# PROC099B_Decoupling_Caps_Reference.net
KiCad netlist of a schematic drawn in Altium Designer
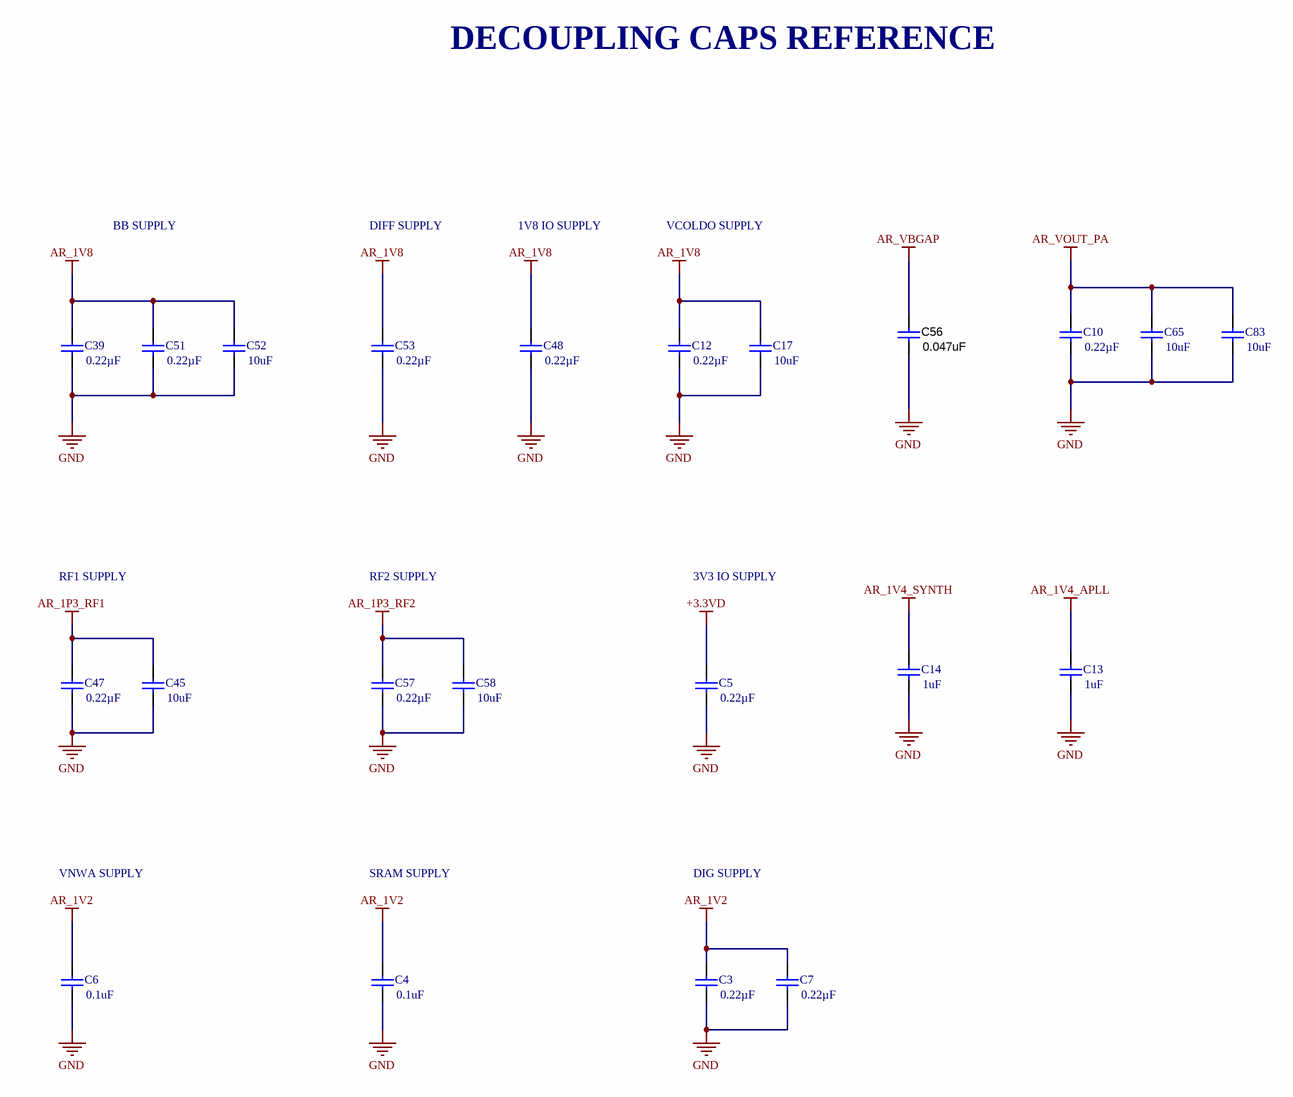
[diagram p0: PROC099B_Decoupling_Caps_Reference.SchDoc]

(export (version "E")
  (design (tool "Eeschema 10.0.6"))
  (components
    (comp (ref "C3")
      (value "GCM155R71C224KE02D")
      (footprint "0402L")
      (description "CAP, CERM, 0.22 µF, 16 V,+/- 10%, X7R, AEC-Q200 Grade 1, 0402")
      (fields (field (name "MANUFACTURER") "MuRata") (field (name "VALUEDISPLAYED") "0.22µF"))
      (libsource (lib "Altium Vault - TI") (part "CMP-0078265-1"))
    )
    (comp (ref "C4")
      (value "GCM155R71C104KA55D")
      (footprint "0402L")
      (description "CAP, CERM, 0.1 uF, 16 V, +/- 10%, X7R, 0402")
      (fields
        (field (name "MANUFACTURER") "MuRata")
        (field (name "VALUEDISPLAYED") "0.1uF")
        (field (name "PUBLISHER") "Texas Instruments")
      )
      (libsource (lib "Altium Vault - TI") (part "CMP-0006351-2"))
    )
    (comp (ref "C5")
      (value "GCM155R71C224KE02D")
      (footprint "0402L")
      (description "CAP, CERM, 0.22 µF, 16 V,+/- 10%, X7R, AEC-Q200 Grade 1, 0402")
      (fields (field (name "MANUFACTURER") "MuRata") (field (name "VALUEDISPLAYED") "0.22µF"))
      (libsource (lib "Altium Vault - TI") (part "CMP-0078265-1"))
    )
    (comp (ref "C6")
      (value "GCM155R71C104KA55D")
      (footprint "0402")
      (description "CAP, CERM, 0.1 uF, 16 V, +/- 10%, X7R, 0402")
      (fields
        (field (name "MANUFACTURER") "MuRata")
        (field (name "VALUEDISPLAYED") "0.1uF")
        (field (name "PUBLISHER") "Texas Instruments")
      )
      (libsource (lib "Altium Vault - TI") (part "Capacitor"))
    )
    (comp (ref "C7")
      (value "GCM155R71C224KE02D")
      (footprint "0402L")
      (description "CAP, CERM, 0.22 µF, 16 V,+/- 10%, X7R, AEC-Q200 Grade 1, 0402")
      (fields (field (name "MANUFACTURER") "MuRata") (field (name "VALUEDISPLAYED") "0.22µF"))
      (libsource (lib "Altium Vault - TI") (part "CMP-0078265-1"))
    )
    (comp (ref "C10")
      (value "GCM155R71C224KE02D")
      (footprint "0402")
      (description "CAP, CERM, 0.22 µF, 16 V,+/- 10%, X7R, AEC-Q200 Grade 1, 0402")
      (fields (field (name "MANUFACTURER") "MuRata") (field (name "VALUEDISPLAYED") "0.22µF"))
      (libsource (lib "Altium Vault - TI") (part "Capacitor"))
    )
    (comp (ref "C12")
      (value "GCM155R71C224KE02D")
      (footprint "0402")
      (description "CAP, CERM, 0.22 µF, 16 V,+/- 10%, X7R, AEC-Q200 Grade 1, 0402")
      (fields (field (name "MANUFACTURER") "MuRata") (field (name "VALUEDISPLAYED") "0.22µF"))
      (libsource (lib "Altium Vault - TI") (part "Capacitor"))
    )
    (comp (ref "C13")
      (value "GCM188R71C105KA64D")
      (footprint "0603")
      (description "CAP, CERM, 1 uF, 16 V, +/- 10%, X7R, AEC-Q200 Grade 1, 0603")
      (fields
        (field (name "MANUFACTURER") "MuRata")
        (field (name "VALUEDISPLAYED") "1uF")
        (field (name "PUBLISHER") "Texas Instruments")
      )
      (libsource (lib "Altium Vault - TI") (part "Capacitor"))
    )
    (comp (ref "C14")
      (value "GCM188R71C105KA64D")
      (footprint "0603")
      (description "CAP, CERM, 1 uF, 16 V, +/- 10%, X7R, AEC-Q200 Grade 1, 0603")
      (fields
        (field (name "MANUFACTURER") "MuRata")
        (field (name "VALUEDISPLAYED") "1uF")
        (field (name "PUBLISHER") "Texas Instruments")
      )
      (libsource (lib "Altium Vault - TI") (part "Capacitor"))
    )
    (comp (ref "C17")
      (value "GCM21BR71A106KE22L")
      (footprint "0805_HV")
      (description "CAP, CERM, 10 uF, 10 V, +/- 10%, X7R, 0805")
      (fields
        (field (name "MANUFACTURER") "MuRata")
        (field (name "VALUEDISPLAYED") "10uF")
        (field (name "PUBLISHER") "Texas Instruments")
      )
      (libsource (lib "Altium Vault - TI") (part "Capacitor"))
    )
    (comp (ref "C39")
      (value "GCM155R71C224KE02D")
      (footprint "0402L")
      (description "CAP, CERM, 0.22 µF, 16 V,+/- 10%, X7R, AEC-Q200 Grade 1, 0402")
      (fields (field (name "MANUFACTURER") "MuRata") (field (name "VALUEDISPLAYED") "0.22µF"))
      (libsource (lib "Altium Vault - TI") (part "CMP-0078265-1"))
    )
    (comp (ref "C45")
      (value "GCM21BR71A106KE22L")
      (footprint "0805_HV1")
      (description "CAP, CERM, 10 uF, 10 V, +/- 10%, X7R, 0805")
      (fields
        (field (name "MANUFACTURER") "MuRata")
        (field (name "VALUEDISPLAYED") "10uF")
        (field (name "PUBLISHER") "Texas Instruments")
      )
      (libsource (lib "Altium Vault - TI") (part "CMP-0008017-2"))
    )
    (comp (ref "C47")
      (value "GCM155R71C224KE02D")
      (footprint "0402L")
      (description "CAP, CERM, 0.22 µF, 16 V,+/- 10%, X7R, AEC-Q200 Grade 1, 0402")
      (fields (field (name "MANUFACTURER") "MuRata") (field (name "VALUEDISPLAYED") "0.22µF"))
      (libsource (lib "Altium Vault - TI") (part "CMP-0078265-1"))
    )
    (comp (ref "C48")
      (value "GCM155R71C224KE02D")
      (footprint "0402")
      (description "CAP, CERM, 0.22 µF, 16 V,+/- 10%, X7R, AEC-Q200 Grade 1, 0402")
      (fields (field (name "MANUFACTURER") "MuRata") (field (name "VALUEDISPLAYED") "0.22µF"))
      (libsource (lib "Altium Vault - TI") (part "Capacitor"))
    )
    (comp (ref "C51")
      (value "GCM155R71C224KE02D")
      (footprint "0402")
      (description "CAP, CERM, 0.22 µF, 16 V,+/- 10%, X7R, AEC-Q200 Grade 1, 0402")
      (fields (field (name "MANUFACTURER") "MuRata") (field (name "VALUEDISPLAYED") "0.22µF"))
      (libsource (lib "Altium Vault - TI") (part "Capacitor"))
    )
    (comp (ref "C52")
      (value "GCM21BR71A106KE22L")
      (footprint "0805_HV")
      (description "CAP, CERM, 10 uF, 10 V, +/- 10%, X7R, 0805")
      (fields
        (field (name "MANUFACTURER") "MuRata")
        (field (name "VALUEDISPLAYED") "10uF")
        (field (name "PUBLISHER") "Texas Instruments")
      )
      (libsource (lib "Altium Vault - TI") (part "Capacitor"))
    )
    (comp (ref "C53")
      (value "GCM155R71C224KE02D")
      (footprint "0402")
      (description "CAP, CERM, 0.22 µF, 16 V,+/- 10%, X7R, AEC-Q200 Grade 1, 0402")
      (fields (field (name "MANUFACTURER") "MuRata") (field (name "VALUEDISPLAYED") "0.22µF"))
      (libsource (lib "Altium Vault - TI") (part "Capacitor"))
    )
    (comp (ref "C56")
      (value "CGA2B3X7R1H473K050BB")
      (footprint "0402")
      (description "CAP, CERM, 0.047 uF, 50 V, +/- 10%, X7R, AEC-Q200 Grade 1, 0402")
      (fields
        (field (name "MANUFACTURER") "TDK")
        (field (name "VALUEDISPLAYED") "0.047uF")
        (field (name "PUBLISHER") "Texas Instruments")
      )
      (libsource (lib "Altium Vault - TI") (part "Capacitor"))
    )
    (comp (ref "C57")
      (value "GCM155R71C224KE02D")
      (footprint "0402")
      (description "CAP, CERM, 0.22 µF, 16 V,+/- 10%, X7R, AEC-Q200 Grade 1, 0402")
      (fields (field (name "MANUFACTURER") "MuRata") (field (name "VALUEDISPLAYED") "0.22µF"))
      (libsource (lib "Altium Vault - TI") (part "Capacitor"))
    )
    (comp (ref "C58")
      (value "GCM21BR71A106KE22L")
      (footprint "0805")
      (description "CAP, CERM, 10 uF, 10 V, +/- 10%, X7R, 0805")
      (fields
        (field (name "MANUFACTURER") "MuRata")
        (field (name "VALUEDISPLAYED") "10uF")
        (field (name "PUBLISHER") "Texas Instruments")
      )
      (libsource (lib "Altium Vault - TI") (part "CMP-0008017-2"))
    )
    (comp (ref "C65")
      (value "GCM21BR71A106KE22L")
      (footprint "0805_HV")
      (description "CAP, CERM, 10 uF, 10 V, +/- 10%, X7R, 0805")
      (fields
        (field (name "MANUFACTURER") "MuRata")
        (field (name "VALUEDISPLAYED") "10uF")
        (field (name "PUBLISHER") "Texas Instruments")
      )
      (libsource (lib "Altium Vault - TI") (part "Capacitor"))
    )
    (comp (ref "C83")
      (value "GCM21BR71A106KE22L")
      (footprint "0805_HV")
      (description "CAP, CERM, 10 uF, 10 V, +/- 10%, X7R, 0805")
      (fields
        (field (name "MANUFACTURER") "MuRata")
        (field (name "VALUEDISPLAYED") "10uF")
        (field (name "PUBLISHER") "Texas Instruments")
      )
      (libsource (lib "Altium Vault - TI") (part "Capacitor"))
    )
  )
  (nets
    (net (code "1") (name "+3.3VD") (class "Default")
      (node (ref "C5") (pin "1") (pinfunction "1_1") (pintype "passive"))
    )
    (net (code "2") (name "AR_1P3_RF1") (class "Default")
      (node (ref "C45") (pin "1") (pinfunction "1_1") (pintype "passive"))
      (node (ref "C47") (pin "1") (pinfunction "1_1") (pintype "passive"))
    )
    (net (code "3") (name "AR_1P3_RF2") (class "Default")
      (node (ref "C57") (pin "1") (pinfunction "1_1") (pintype "passive"))
      (node (ref "C58") (pin "1") (pinfunction "1_1") (pintype "passive"))
    )
    (net (code "4") (name "AR_1V2") (class "Default")
      (node (ref "C3") (pin "1") (pinfunction "1_1") (pintype "passive"))
      (node (ref "C4") (pin "1") (pinfunction "1_1") (pintype "passive"))
      (node (ref "C6") (pin "1") (pinfunction "1_1") (pintype "passive"))
      (node (ref "C7") (pin "1") (pinfunction "1_1") (pintype "passive"))
    )
    (net (code "5") (name "AR_1V4_APLL") (class "Default")
      (node (ref "C13") (pin "1") (pinfunction "1_1") (pintype "passive"))
    )
    (net (code "6") (name "AR_1V4_SYNTH") (class "Default")
      (node (ref "C14") (pin "1") (pinfunction "1_1") (pintype "passive"))
    )
    (net (code "7") (name "AR_1V8") (class "Default")
      (node (ref "C12") (pin "1") (pinfunction "1_1") (pintype "passive"))
      (node (ref "C17") (pin "1") (pinfunction "1_1") (pintype "passive"))
      (node (ref "C39") (pin "1") (pinfunction "1_1") (pintype "passive"))
      (node (ref "C48") (pin "1") (pinfunction "1_1") (pintype "passive"))
      (node (ref "C51") (pin "1") (pinfunction "1_1") (pintype "passive"))
      (node (ref "C52") (pin "1") (pinfunction "1_1") (pintype "passive"))
      (node (ref "C53") (pin "1") (pinfunction "1_1") (pintype "passive"))
    )
    (net (code "8") (name "AR_VBGAP") (class "Default")
      (node (ref "C56") (pin "1") (pinfunction "1_1") (pintype "passive"))
    )
    (net (code "9") (name "AR_VOUT_PA") (class "Default")
      (node (ref "C10") (pin "1") (pinfunction "1_1") (pintype "passive"))
      (node (ref "C65") (pin "1") (pinfunction "1_1") (pintype "passive"))
      (node (ref "C83") (pin "1") (pinfunction "1_1") (pintype "passive"))
    )
    (net (code "10") (name "GND") (class "Default")
      (node (ref "C10") (pin "2") (pinfunction "2_2") (pintype "passive"))
      (node (ref "C12") (pin "2") (pinfunction "2_2") (pintype "passive"))
      (node (ref "C13") (pin "2") (pinfunction "2_2") (pintype "passive"))
      (node (ref "C14") (pin "2") (pinfunction "2_2") (pintype "passive"))
      (node (ref "C17") (pin "2") (pinfunction "2_2") (pintype "passive"))
      (node (ref "C3") (pin "2") (pinfunction "2_2") (pintype "passive"))
      (node (ref "C39") (pin "2") (pinfunction "2_2") (pintype "passive"))
      (node (ref "C4") (pin "2") (pinfunction "2_2") (pintype "passive"))
      (node (ref "C45") (pin "2") (pinfunction "2_2") (pintype "passive"))
      (node (ref "C47") (pin "2") (pinfunction "2_2") (pintype "passive"))
      (node (ref "C48") (pin "2") (pinfunction "2_2") (pintype "passive"))
      (node (ref "C5") (pin "2") (pinfunction "2_2") (pintype "passive"))
      (node (ref "C51") (pin "2") (pinfunction "2_2") (pintype "passive"))
      (node (ref "C52") (pin "2") (pinfunction "2_2") (pintype "passive"))
      (node (ref "C53") (pin "2") (pinfunction "2_2") (pintype "passive"))
      (node (ref "C56") (pin "2") (pinfunction "2_2") (pintype "passive"))
      (node (ref "C57") (pin "2") (pinfunction "2_2") (pintype "passive"))
      (node (ref "C58") (pin "2") (pinfunction "2_2") (pintype "passive"))
      (node (ref "C6") (pin "2") (pinfunction "2_2") (pintype "passive"))
      (node (ref "C65") (pin "2") (pinfunction "2_2") (pintype "passive"))
      (node (ref "C7") (pin "2") (pinfunction "2_2") (pintype "passive"))
      (node (ref "C83") (pin "2") (pinfunction "2_2") (pintype "passive"))
    )
  )
)
